# qo-100-rf-switch.net
KiCad netlist of a schematic drawn in EAGLE
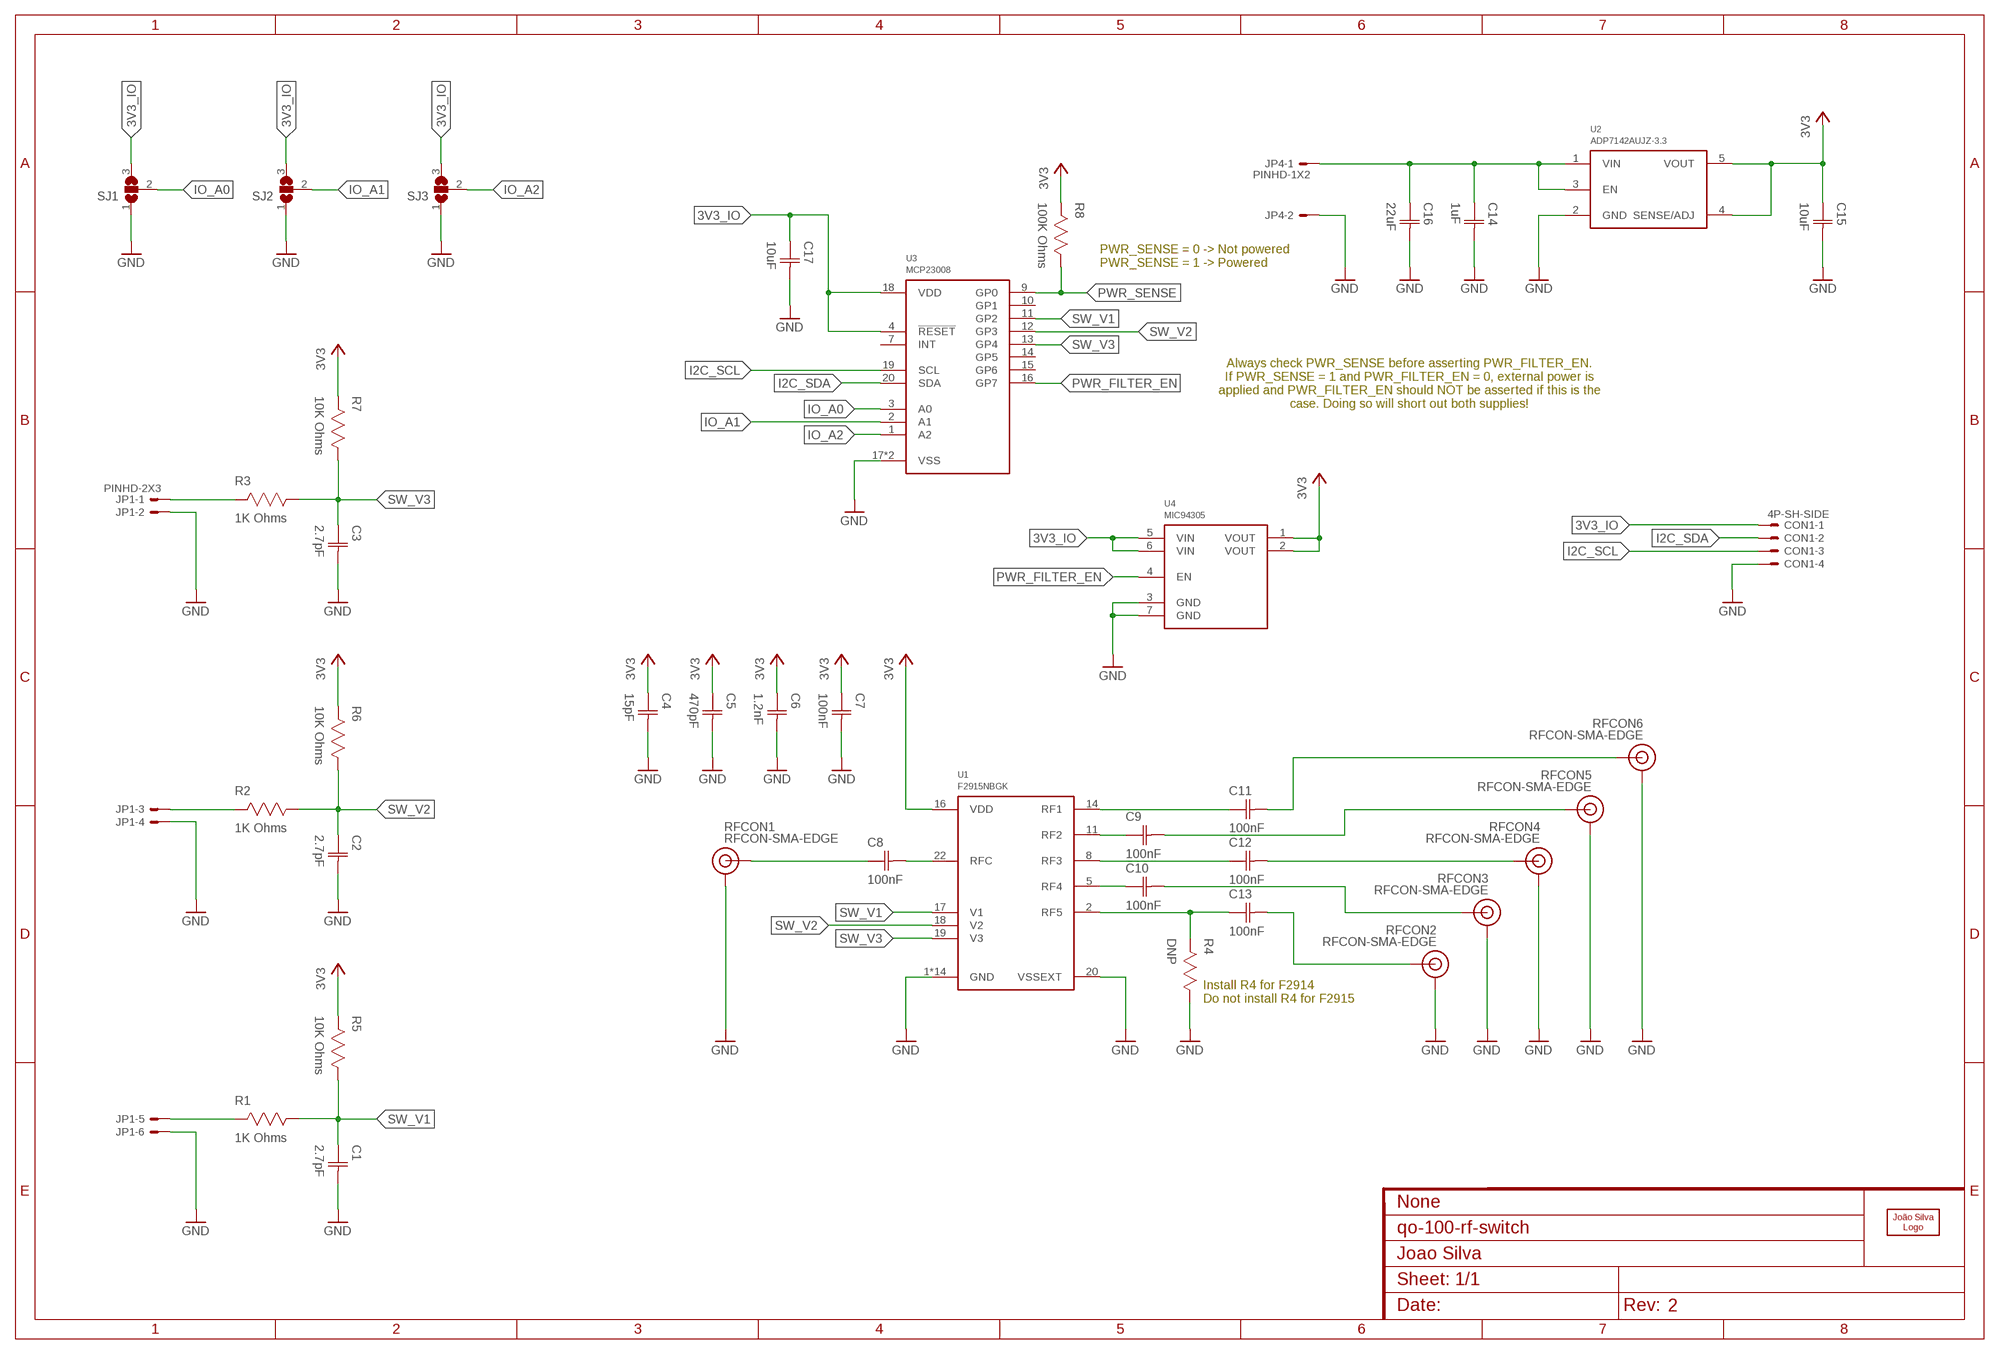
[diagram p0: schematic, sheet 1]

(export (version "E")
  (design (tool "Eeschema 10.0.6"))
  (components
    (comp (ref "C1")
      (value "2.7pF")
      (footprint "eagle-import:CAP0603")
      (libsource (lib "eagle-import") (part "CAPACITOR-0603"))
    )
    (comp (ref "C2")
      (value "2.7pF")
      (footprint "eagle-import:CAP0603")
      (libsource (lib "eagle-import") (part "CAPACITOR-0603"))
    )
    (comp (ref "C3")
      (value "2.7pF")
      (footprint "eagle-import:CAP0603")
      (libsource (lib "eagle-import") (part "CAPACITOR-0603"))
    )
    (comp (ref "C4")
      (value "15pF")
      (footprint "eagle-import:CAP0603")
      (libsource (lib "eagle-import") (part "CAPACITOR-0603"))
    )
    (comp (ref "C5")
      (value "470pF")
      (footprint "eagle-import:CAP0603")
      (libsource (lib "eagle-import") (part "CAPACITOR-0603"))
    )
    (comp (ref "C6")
      (value "1.2nF")
      (footprint "eagle-import:CAP0603")
      (libsource (lib "eagle-import") (part "CAPACITOR-0603"))
    )
    (comp (ref "C7")
      (value "100nF")
      (footprint "eagle-import:CAP0603")
      (libsource (lib "eagle-import") (part "CAPACITOR-0603"))
    )
    (comp (ref "C8")
      (value "100nF")
      (footprint "eagle-import:CAP0603")
      (libsource (lib "eagle-import") (part "CAPACITOR-0603"))
    )
    (comp (ref "C9")
      (value "100nF")
      (footprint "eagle-import:CAP0603")
      (libsource (lib "eagle-import") (part "CAPACITOR-0603"))
    )
    (comp (ref "C10")
      (value "100nF")
      (footprint "eagle-import:CAP0603")
      (libsource (lib "eagle-import") (part "CAPACITOR-0603"))
    )
    (comp (ref "C11")
      (value "100nF")
      (footprint "eagle-import:CAP0603")
      (libsource (lib "eagle-import") (part "CAPACITOR-0603"))
    )
    (comp (ref "C12")
      (value "100nF")
      (footprint "eagle-import:CAP0603")
      (libsource (lib "eagle-import") (part "CAPACITOR-0603"))
    )
    (comp (ref "C13")
      (value "100nF")
      (footprint "eagle-import:CAP0603")
      (libsource (lib "eagle-import") (part "CAPACITOR-0603"))
    )
    (comp (ref "C14")
      (value "1uF")
      (footprint "eagle-import:CAP0603")
      (libsource (lib "eagle-import") (part "CAPACITOR-0603"))
    )
    (comp (ref "C15")
      (value "10uF")
      (footprint "eagle-import:CAP0603")
      (libsource (lib "eagle-import") (part "CAPACITOR-0603"))
    )
    (comp (ref "C16")
      (value "22uF")
      (footprint "eagle-import:CAP1206")
      (libsource (lib "eagle-import") (part "CAPACITOR-1206"))
    )
    (comp (ref "C17")
      (value "10uF")
      (footprint "eagle-import:CAP0603")
      (libsource (lib "eagle-import") (part "CAPACITOR-0603"))
    )
    (comp (ref "CON1")
      (value "4P-SH-SIDE")
      (footprint "eagle-import:SH-04-SIDE")
      (libsource (lib "eagle-import") (part "4P-SH-SIDE"))
    )
    (comp (ref "JP1")
      (value "PINHD-2X3")
      (footprint "eagle-import:2X03")
      (libsource (lib "eagle-import") (part "PINHD-2X3"))
    )
    (comp (ref "JP4")
      (value "PINHD-1X2")
      (footprint "eagle-import:1X02")
      (libsource (lib "eagle-import") (part "PINHD-1X2"))
    )
    (comp (ref "LOGO1")
      (value "JS-5MM")
      (footprint "eagle-import:JS_5MM")
      (libsource (lib "eagle-import") (part "JS-5MM"))
    )
    (comp (ref "R1")
      (value "1K Ohms")
      (footprint "eagle-import:RES0603")
      (libsource (lib "eagle-import") (part "RESISTOR-0603"))
    )
    (comp (ref "R2")
      (value "1K Ohms")
      (footprint "eagle-import:RES0603")
      (libsource (lib "eagle-import") (part "RESISTOR-0603"))
    )
    (comp (ref "R3")
      (value "1K Ohms")
      (footprint "eagle-import:RES0603")
      (libsource (lib "eagle-import") (part "RESISTOR-0603"))
    )
    (comp (ref "R4")
      (value "DNP")
      (footprint "eagle-import:RES0603")
      (libsource (lib "eagle-import") (part "RESISTOR-0603"))
    )
    (comp (ref "R5")
      (value "10K Ohms")
      (footprint "eagle-import:RES0603")
      (libsource (lib "eagle-import") (part "RESISTOR-0603"))
    )
    (comp (ref "R6")
      (value "10K Ohms")
      (footprint "eagle-import:RES0603")
      (libsource (lib "eagle-import") (part "RESISTOR-0603"))
    )
    (comp (ref "R7")
      (value "10K Ohms")
      (footprint "eagle-import:RES0603")
      (libsource (lib "eagle-import") (part "RESISTOR-0603"))
    )
    (comp (ref "R8")
      (value "100K Ohms")
      (footprint "eagle-import:RES0603")
      (libsource (lib "eagle-import") (part "RESISTOR-0603"))
    )
    (comp (ref "RFCON1")
      (value "RFCON-SMA-EDGE")
      (footprint "eagle-import:SMA-EDGE")
      (libsource (lib "eagle-import") (part "RFCON-SMA-EDGE"))
    )
    (comp (ref "RFCON2")
      (value "RFCON-SMA-EDGE")
      (footprint "eagle-import:SMA-EDGE")
      (libsource (lib "eagle-import") (part "RFCON-SMA-EDGE"))
    )
    (comp (ref "RFCON3")
      (value "RFCON-SMA-EDGE")
      (footprint "eagle-import:SMA-EDGE")
      (libsource (lib "eagle-import") (part "RFCON-SMA-EDGE"))
    )
    (comp (ref "RFCON4")
      (value "RFCON-SMA-EDGE")
      (footprint "eagle-import:SMA-EDGE")
      (libsource (lib "eagle-import") (part "RFCON-SMA-EDGE"))
    )
    (comp (ref "RFCON5")
      (value "RFCON-SMA-EDGE")
      (footprint "eagle-import:SMA-EDGE")
      (libsource (lib "eagle-import") (part "RFCON-SMA-EDGE"))
    )
    (comp (ref "RFCON6")
      (value "RFCON-SMA-EDGE")
      (footprint "eagle-import:SMA-EDGE")
      (libsource (lib "eagle-import") (part "RFCON-SMA-EDGE"))
    )
    (comp (ref "SJ1")
      (value "SJ2S")
      (footprint "eagle-import:SJ2_S")
      (libsource (lib "eagle-import") (part "SJ2S"))
    )
    (comp (ref "SJ2")
      (value "SJ2S")
      (footprint "eagle-import:SJ2_S")
      (libsource (lib "eagle-import") (part "SJ2S"))
    )
    (comp (ref "SJ3")
      (value "SJ2S")
      (footprint "eagle-import:SJ2_S")
      (libsource (lib "eagle-import") (part "SJ2S"))
    )
    (comp (ref "U1")
      (value "F2915NBGK")
      (footprint "eagle-import:QFN24")
      (libsource (lib "eagle-import") (part "F2915NBGK"))
    )
    (comp (ref "U2")
      (value "ADP7142AUJZ-3.3")
      (footprint "eagle-import:SOT23-5")
      (libsource (lib "eagle-import") (part "ADP7142AUJZ-3.3"))
    )
    (comp (ref "U3")
      (value "MCP23008")
      (footprint "eagle-import:QFN20")
      (libsource (lib "eagle-import") (part "MCP23008"))
    )
    (comp (ref "U4")
      (value "MIC94305")
      (footprint "eagle-import:DFN6")
      (libsource (lib "eagle-import") (part "MIC94305"))
    )
  )
  (nets
    (net (code "1") (name "3V3") (class "Default")
      (node (ref "C15") (pin "1") (pinfunction "C1_1") (pintype "passive"))
      (node (ref "C4") (pin "1") (pinfunction "C1_1") (pintype "passive"))
      (node (ref "C5") (pin "1") (pinfunction "C1_1") (pintype "passive"))
      (node (ref "C6") (pin "1") (pinfunction "C1_1") (pintype "passive"))
      (node (ref "C7") (pin "1") (pinfunction "C1_1") (pintype "passive"))
      (node (ref "R5") (pin "2") (pinfunction "2_2") (pintype "passive"))
      (node (ref "R6") (pin "2") (pinfunction "2_2") (pintype "passive"))
      (node (ref "R7") (pin "2") (pinfunction "2_2") (pintype "passive"))
      (node (ref "R8") (pin "2") (pinfunction "2_2") (pintype "passive"))
      (node (ref "U1") (pin "16") (pinfunction "VDD_16") (pintype "bidirectional"))
      (node (ref "U2") (pin "4") (pinfunction "SENSE/ADJ_4") (pintype "bidirectional"))
      (node (ref "U2") (pin "5") (pinfunction "VOUT_5") (pintype "bidirectional"))
      (node (ref "U4") (pin "1") (pinfunction "VOUT_1") (pintype "bidirectional"))
      (node (ref "U4") (pin "2") (pinfunction "VOUT_2") (pintype "bidirectional"))
    )
    (net (code "2") (name "3V3_IO") (class "Default")
      (node (ref "C17") (pin "1") (pinfunction "C1_1") (pintype "passive"))
      (node (ref "CON1") (pin "1") (pinfunction "S_1") (pintype "passive"))
      (node (ref "SJ1") (pin "3") (pinfunction "3_3") (pintype "passive"))
      (node (ref "SJ2") (pin "3") (pinfunction "3_3") (pintype "passive"))
      (node (ref "SJ3") (pin "3") (pinfunction "3_3") (pintype "passive"))
      (node (ref "U3") (pin "18") (pinfunction "VDD_18") (pintype "bidirectional"))
      (node (ref "U3") (pin "4") (pinfunction "~{RESET}_4") (pintype "bidirectional"))
      (node (ref "U4") (pin "5") (pinfunction "VIN_5") (pintype "bidirectional"))
      (node (ref "U4") (pin "6") (pinfunction "VIN_6") (pintype "bidirectional"))
    )
    (net (code "3") (name "GND") (class "Default")
      (node (ref "C1") (pin "2") (pinfunction "C2_2") (pintype "passive"))
      (node (ref "C14") (pin "2") (pinfunction "C2_2") (pintype "passive"))
      (node (ref "C15") (pin "2") (pinfunction "C2_2") (pintype "passive"))
      (node (ref "C16") (pin "2") (pinfunction "C2_2") (pintype "passive"))
      (node (ref "C17") (pin "2") (pinfunction "C2_2") (pintype "passive"))
      (node (ref "C2") (pin "2") (pinfunction "C2_2") (pintype "passive"))
      (node (ref "C3") (pin "2") (pinfunction "C2_2") (pintype "passive"))
      (node (ref "C4") (pin "2") (pinfunction "C2_2") (pintype "passive"))
      (node (ref "C5") (pin "2") (pinfunction "C2_2") (pintype "passive"))
      (node (ref "C6") (pin "2") (pinfunction "C2_2") (pintype "passive"))
      (node (ref "C7") (pin "2") (pinfunction "C2_2") (pintype "passive"))
      (node (ref "CON1") (pin "4") (pinfunction "S_4") (pintype "passive"))
      (node (ref "JP1") (pin "2") (pinfunction "S_2") (pintype "passive"))
      (node (ref "JP1") (pin "4") (pinfunction "S_4") (pintype "passive"))
      (node (ref "JP1") (pin "6") (pinfunction "S_6") (pintype "passive"))
      (node (ref "JP4") (pin "2") (pinfunction "S_2") (pintype "passive"))
      (node (ref "R4") (pin "1") (pinfunction "1_1") (pintype "passive"))
      (node (ref "RFCON1") (pin "GND@0") (pinfunction "GND_GND@0") (pintype "bidirectional"))
      (node (ref "RFCON1") (pin "GND@1") (pinfunction "GND_GND@1") (pintype "bidirectional"))
      (node (ref "RFCON1") (pin "GND@2") (pinfunction "GND_GND@2") (pintype "bidirectional"))
      (node (ref "RFCON1") (pin "GND@3") (pinfunction "GND_GND@3") (pintype "bidirectional"))
      (node (ref "RFCON2") (pin "GND@0") (pinfunction "GND_GND@0") (pintype "bidirectional"))
      (node (ref "RFCON2") (pin "GND@1") (pinfunction "GND_GND@1") (pintype "bidirectional"))
      (node (ref "RFCON2") (pin "GND@2") (pinfunction "GND_GND@2") (pintype "bidirectional"))
      (node (ref "RFCON2") (pin "GND@3") (pinfunction "GND_GND@3") (pintype "bidirectional"))
      (node (ref "RFCON3") (pin "GND@0") (pinfunction "GND_GND@0") (pintype "bidirectional"))
      (node (ref "RFCON3") (pin "GND@1") (pinfunction "GND_GND@1") (pintype "bidirectional"))
      (node (ref "RFCON3") (pin "GND@2") (pinfunction "GND_GND@2") (pintype "bidirectional"))
      (node (ref "RFCON3") (pin "GND@3") (pinfunction "GND_GND@3") (pintype "bidirectional"))
      (node (ref "RFCON4") (pin "GND@0") (pinfunction "GND_GND@0") (pintype "bidirectional"))
      (node (ref "RFCON4") (pin "GND@1") (pinfunction "GND_GND@1") (pintype "bidirectional"))
      (node (ref "RFCON4") (pin "GND@2") (pinfunction "GND_GND@2") (pintype "bidirectional"))
      (node (ref "RFCON4") (pin "GND@3") (pinfunction "GND_GND@3") (pintype "bidirectional"))
      (node (ref "RFCON5") (pin "GND@0") (pinfunction "GND_GND@0") (pintype "bidirectional"))
      (node (ref "RFCON5") (pin "GND@1") (pinfunction "GND_GND@1") (pintype "bidirectional"))
      (node (ref "RFCON5") (pin "GND@2") (pinfunction "GND_GND@2") (pintype "bidirectional"))
      (node (ref "RFCON5") (pin "GND@3") (pinfunction "GND_GND@3") (pintype "bidirectional"))
      (node (ref "RFCON6") (pin "GND@0") (pinfunction "GND_GND@0") (pintype "bidirectional"))
      (node (ref "RFCON6") (pin "GND@1") (pinfunction "GND_GND@1") (pintype "bidirectional"))
      (node (ref "RFCON6") (pin "GND@2") (pinfunction "GND_GND@2") (pintype "bidirectional"))
      (node (ref "RFCON6") (pin "GND@3") (pinfunction "GND_GND@3") (pintype "bidirectional"))
      (node (ref "SJ1") (pin "1") (pinfunction "1_1") (pintype "passive"))
      (node (ref "SJ2") (pin "1") (pinfunction "1_1") (pintype "passive"))
      (node (ref "SJ3") (pin "1") (pinfunction "1_1") (pintype "passive"))
      (node (ref "U1") (pin "1") (pinfunction "GND_1") (pintype "bidirectional"))
      (node (ref "U1") (pin "10") (pinfunction "GND_10") (pintype "bidirectional"))
      (node (ref "U1") (pin "12") (pinfunction "GND_12") (pintype "bidirectional"))
      (node (ref "U1") (pin "13") (pinfunction "GND_13") (pintype "bidirectional"))
      (node (ref "U1") (pin "15") (pinfunction "GND_15") (pintype "bidirectional"))
      (node (ref "U1") (pin "20") (pinfunction "VSSEXT_20") (pintype "bidirectional"))
      (node (ref "U1") (pin "21") (pinfunction "GND_21") (pintype "bidirectional"))
      (node (ref "U1") (pin "23") (pinfunction "GND_23") (pintype "bidirectional"))
      (node (ref "U1") (pin "24") (pinfunction "GND_24") (pintype "bidirectional"))
      (node (ref "U1") (pin "25") (pinfunction "GND_25") (pintype "bidirectional"))
      (node (ref "U1") (pin "3") (pinfunction "GND_3") (pintype "bidirectional"))
      (node (ref "U1") (pin "4") (pinfunction "GND_4") (pintype "bidirectional"))
      (node (ref "U1") (pin "6") (pinfunction "GND_6") (pintype "bidirectional"))
      (node (ref "U1") (pin "7") (pinfunction "GND_7") (pintype "bidirectional"))
      (node (ref "U1") (pin "9") (pinfunction "GND_9") (pintype "bidirectional"))
      (node (ref "U2") (pin "2") (pinfunction "GND_2") (pintype "bidirectional"))
      (node (ref "U3") (pin "17") (pinfunction "VSS_17") (pintype "bidirectional"))
      (node (ref "U3") (pin "PAD") (pinfunction "VSS_PAD") (pintype "bidirectional"))
      (node (ref "U4") (pin "3") (pinfunction "GND_3") (pintype "bidirectional"))
      (node (ref "U4") (pin "7") (pinfunction "GND_7") (pintype "bidirectional"))
    )
    (net (code "4") (name "I2C_SCL") (class "Default")
      (node (ref "CON1") (pin "3") (pinfunction "S_3") (pintype "passive"))
      (node (ref "U3") (pin "19") (pinfunction "SCL_19") (pintype "bidirectional"))
    )
    (net (code "5") (name "I2C_SDA") (class "Default")
      (node (ref "CON1") (pin "2") (pinfunction "S_2") (pintype "passive"))
      (node (ref "U3") (pin "20") (pinfunction "SDA_20") (pintype "bidirectional"))
    )
    (net (code "6") (name "IO_A0") (class "Default")
      (node (ref "SJ1") (pin "2") (pinfunction "2_2") (pintype "passive"))
      (node (ref "U3") (pin "3") (pinfunction "A0_3") (pintype "bidirectional"))
    )
    (net (code "7") (name "IO_A1") (class "Default")
      (node (ref "SJ2") (pin "2") (pinfunction "2_2") (pintype "passive"))
      (node (ref "U3") (pin "2") (pinfunction "A1_2") (pintype "bidirectional"))
    )
    (net (code "8") (name "IO_A2") (class "Default")
      (node (ref "SJ3") (pin "2") (pinfunction "2_2") (pintype "passive"))
      (node (ref "U3") (pin "1") (pinfunction "A2_1") (pintype "bidirectional"))
    )
    (net (code "9") (name "Net-(C8-C1)") (class "Default")
      (node (ref "C8") (pin "1") (pinfunction "C1_1") (pintype "passive"))
      (node (ref "RFCON1") (pin "SIG") (pinfunction "SIGNAL_SIG") (pintype "bidirectional"))
    )
    (net (code "10") (name "Net-(C8-C2)") (class "Default")
      (node (ref "C8") (pin "2") (pinfunction "C2_2") (pintype "passive"))
      (node (ref "U1") (pin "22") (pinfunction "RFC_22") (pintype "bidirectional"))
    )
    (net (code "11") (name "Net-(C9-C1)") (class "Default")
      (node (ref "C9") (pin "1") (pinfunction "C1_1") (pintype "passive"))
      (node (ref "U1") (pin "11") (pinfunction "RF2_11") (pintype "bidirectional"))
    )
    (net (code "12") (name "Net-(C9-C2)") (class "Default")
      (node (ref "C9") (pin "2") (pinfunction "C2_2") (pintype "passive"))
      (node (ref "RFCON5") (pin "SIG") (pinfunction "SIGNAL_SIG") (pintype "bidirectional"))
    )
    (net (code "13") (name "Net-(C10-C1)") (class "Default")
      (node (ref "C10") (pin "1") (pinfunction "C1_1") (pintype "passive"))
      (node (ref "U1") (pin "5") (pinfunction "RF4_5") (pintype "bidirectional"))
    )
    (net (code "14") (name "Net-(C10-C2)") (class "Default")
      (node (ref "C10") (pin "2") (pinfunction "C2_2") (pintype "passive"))
      (node (ref "RFCON3") (pin "SIG") (pinfunction "SIGNAL_SIG") (pintype "bidirectional"))
    )
    (net (code "15") (name "Net-(C11-C1)") (class "Default")
      (node (ref "C11") (pin "1") (pinfunction "C1_1") (pintype "passive"))
      (node (ref "U1") (pin "14") (pinfunction "RF1_14") (pintype "bidirectional"))
    )
    (net (code "16") (name "Net-(C11-C2)") (class "Default")
      (node (ref "C11") (pin "2") (pinfunction "C2_2") (pintype "passive"))
      (node (ref "RFCON6") (pin "SIG") (pinfunction "SIGNAL_SIG") (pintype "bidirectional"))
    )
    (net (code "17") (name "Net-(C12-C1)") (class "Default")
      (node (ref "C12") (pin "1") (pinfunction "C1_1") (pintype "passive"))
      (node (ref "U1") (pin "8") (pinfunction "RF3_8") (pintype "bidirectional"))
    )
    (net (code "18") (name "Net-(C12-C2)") (class "Default")
      (node (ref "C12") (pin "2") (pinfunction "C2_2") (pintype "passive"))
      (node (ref "RFCON4") (pin "SIG") (pinfunction "SIGNAL_SIG") (pintype "bidirectional"))
    )
    (net (code "19") (name "Net-(C13-C1)") (class "Default")
      (node (ref "C13") (pin "1") (pinfunction "C1_1") (pintype "passive"))
      (node (ref "R4") (pin "2") (pinfunction "2_2") (pintype "passive"))
      (node (ref "U1") (pin "2") (pinfunction "RF5_2") (pintype "bidirectional"))
    )
    (net (code "20") (name "Net-(C13-C2)") (class "Default")
      (node (ref "C13") (pin "2") (pinfunction "C2_2") (pintype "passive"))
      (node (ref "RFCON2") (pin "SIG") (pinfunction "SIGNAL_SIG") (pintype "bidirectional"))
    )
    (net (code "21") (name "Net-(C14-C1)") (class "Default")
      (node (ref "C14") (pin "1") (pinfunction "C1_1") (pintype "passive"))
      (node (ref "C16") (pin "1") (pinfunction "C1_1") (pintype "passive"))
      (node (ref "JP4") (pin "1") (pinfunction "S_1") (pintype "passive"))
      (node (ref "U2") (pin "1") (pinfunction "VIN_1") (pintype "bidirectional"))
      (node (ref "U2") (pin "3") (pinfunction "EN_3") (pintype "bidirectional"))
    )
    (net (code "22") (name "Net-(JP1A-S)") (class "Default")
      (node (ref "JP1") (pin "1") (pinfunction "S_1") (pintype "passive"))
      (node (ref "R3") (pin "2") (pinfunction "2_2") (pintype "passive"))
    )
    (net (code "23") (name "Net-(JP1C-S)") (class "Default")
      (node (ref "JP1") (pin "3") (pinfunction "S_3") (pintype "passive"))
      (node (ref "R2") (pin "2") (pinfunction "2_2") (pintype "passive"))
    )
    (net (code "24") (name "Net-(JP1E-S)") (class "Default")
      (node (ref "JP1") (pin "5") (pinfunction "S_5") (pintype "passive"))
      (node (ref "R1") (pin "2") (pinfunction "2_2") (pintype "passive"))
    )
    (net (code "25") (name "PWR_FILTER_EN") (class "Default")
      (node (ref "U3") (pin "16") (pinfunction "GP7_16") (pintype "bidirectional"))
      (node (ref "U4") (pin "4") (pinfunction "EN_4") (pintype "bidirectional"))
    )
    (net (code "26") (name "PWR_SENSE") (class "Default")
      (node (ref "R8") (pin "1") (pinfunction "1_1") (pintype "passive"))
      (node (ref "U3") (pin "9") (pinfunction "GP0_9") (pintype "bidirectional"))
    )
    (net (code "27") (name "SW_V1") (class "Default")
      (node (ref "C1") (pin "1") (pinfunction "C1_1") (pintype "passive"))
      (node (ref "R1") (pin "1") (pinfunction "1_1") (pintype "passive"))
      (node (ref "R5") (pin "1") (pinfunction "1_1") (pintype "passive"))
      (node (ref "U1") (pin "17") (pinfunction "V1_17") (pintype "bidirectional"))
      (node (ref "U3") (pin "11") (pinfunction "GP2_11") (pintype "bidirectional"))
    )
    (net (code "28") (name "SW_V2") (class "Default")
      (node (ref "C2") (pin "1") (pinfunction "C1_1") (pintype "passive"))
      (node (ref "R2") (pin "1") (pinfunction "1_1") (pintype "passive"))
      (node (ref "R6") (pin "1") (pinfunction "1_1") (pintype "passive"))
      (node (ref "U1") (pin "18") (pinfunction "V2_18") (pintype "bidirectional"))
      (node (ref "U3") (pin "12") (pinfunction "GP3_12") (pintype "bidirectional"))
    )
    (net (code "29") (name "SW_V3") (class "Default")
      (node (ref "C3") (pin "1") (pinfunction "C1_1") (pintype "passive"))
      (node (ref "R3") (pin "1") (pinfunction "1_1") (pintype "passive"))
      (node (ref "R7") (pin "1") (pinfunction "1_1") (pintype "passive"))
      (node (ref "U1") (pin "19") (pinfunction "V3_19") (pintype "bidirectional"))
      (node (ref "U3") (pin "13") (pinfunction "GP4_13") (pintype "bidirectional"))
    )
    (net (code "30") (name "unconnected-(U3-GP1-Pad10)") (class "Default")
      (node (ref "U3") (pin "10") (pinfunction "GP1_10") (pintype "bidirectional"))
    )
    (net (code "31") (name "unconnected-(U3-GP5-Pad14)") (class "Default")
      (node (ref "U3") (pin "14") (pinfunction "GP5_14") (pintype "bidirectional"))
    )
    (net (code "32") (name "unconnected-(U3-GP6-Pad15)") (class "Default")
      (node (ref "U3") (pin "15") (pinfunction "GP6_15") (pintype "bidirectional"))
    )
    (net (code "33") (name "unconnected-(U3-INT-Pad7)") (class "Default")
      (node (ref "U3") (pin "7") (pinfunction "INT_7") (pintype "bidirectional"))
    )
  )
)
